# cc2651r3.net
KiCad netlist of a schematic drawn in EAGLE
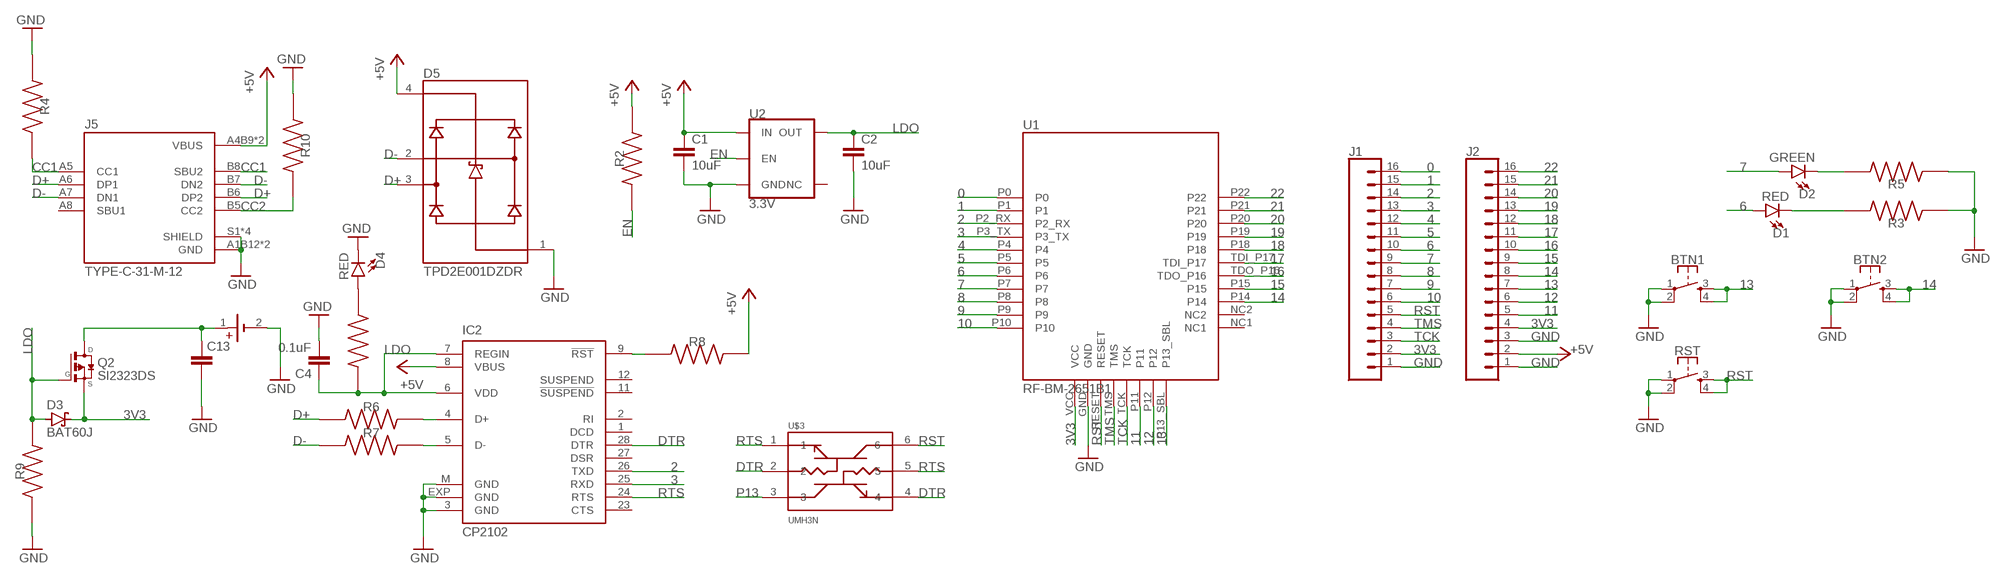
[diagram p0: schematic, sheet 1]

(export (version "E")
  (design (tool "Eeschema 10.0.6"))
  (components
    (comp (ref "BT2")
      (value "79527141")
      (footprint "eagle-import:79527141")
      (fields
        (field (name "DIGIKEY_PART_NO") "732-12325-2-ND")
        (field (name "MANUFACTURER") "Wurth Electronics Inc.")
        (field (name "CREATED_BY") "PCBLayout.com")
      )
      (libsource (lib "eagle-import") (part "79527141"))
    )
    (comp (ref "BTN1")
      (value "MOMENTARY-SWITCH-SPST-2-SMD-4.6X2.8MM")
      (footprint "eagle-import:TACTILE_SWITCH_SMD_4.6X2.8MM")
      (libsource (lib "eagle-import") (part "MOMENTARY-SWITCH-SPST-2-SMD-4.6X2.8MM"))
    )
    (comp (ref "BTN2")
      (value "MOMENTARY-SWITCH-SPST-2-SMD-4.6X2.8MM")
      (footprint "eagle-import:TACTILE_SWITCH_SMD_4.6X2.8MM")
      (libsource (lib "eagle-import") (part "MOMENTARY-SWITCH-SPST-2-SMD-4.6X2.8MM"))
    )
    (comp (ref "C1")
      (value "10uF")
      (footprint "eagle-import:0603")
      (libsource (lib "eagle-import") (part "10UF-0603-6.3V-20%"))
    )
    (comp (ref "C2")
      (value "10uF")
      (footprint "eagle-import:0603")
      (libsource (lib "eagle-import") (part "10UF-0603-6.3V-20%"))
    )
    (comp (ref "C4")
      (value "0.1uF")
      (footprint "eagle-import:0603")
      (libsource (lib "eagle-import") (part "0.1UF-0603-25V-(+80/-20%)"))
    )
    (comp (ref "C13")
      (value "C_TANTALUM-2917(7343-METRIC)")
      (footprint "eagle-import:CAPM7343X310")
      (libsource (lib "eagle-import") (part "CTANTALUM-2917(7343-METRIC)_"))
    )
    (comp (ref "D1")
      (value "RED")
      (footprint "eagle-import:LED-0603")
      (libsource (lib "eagle-import") (part "LED-RED0603"))
    )
    (comp (ref "D2")
      (value "GREEN")
      (footprint "eagle-import:LED-0603")
      (libsource (lib "eagle-import") (part "LED-GREEN0603"))
    )
    (comp (ref "D3")
      (value "BAT60J")
      (footprint "eagle-import:SOD323_ST")
      (libsource (lib "eagle-import") (part "BAT60J"))
    )
    (comp (ref "D4")
      (value "RED")
      (footprint "eagle-import:LED-0603")
      (libsource (lib "eagle-import") (part "LED-RED0603"))
    )
    (comp (ref "D5")
      (value "TPD2E001DZDR")
      (footprint "eagle-import:SOT192P237X122-4N")
      (fields (field (name "MF") "Texas Instruments"))
      (libsource (lib "eagle-import") (part "TPD2E001DZDR"))
    )
    (comp (ref "IC2")
      (value "CP2102")
      (footprint "eagle-import:MLP28")
      (fields (field (name "MF") "FARNELL") (field (name "MPN") "CP2102-GM"))
      (libsource (lib "eagle-import") (part "CP2102"))
    )
    (comp (ref "J1")
      (value "CONN_161X16_NO_SILK")
      (footprint "eagle-import:1X16_NO_SILK")
      (libsource (lib "eagle-import") (part "CONN_161X16_NO_SILK"))
    )
    (comp (ref "J2")
      (value "CONN_161X16_NO_SILK")
      (footprint "eagle-import:1X16_NO_SILK")
      (libsource (lib "eagle-import") (part "CONN_161X16_NO_SILK"))
    )
    (comp (ref "J5")
      (value "TYPE-C-31-M-12")
      (footprint "eagle-import:HRO_TYPE-C-31-M-12")
      (fields (field (name "MF") "HRO Electronics Co., Ltd."))
      (libsource (lib "eagle-import") (part "TYPE-C-31-M-12"))
    )
    (comp (ref "Q2")
      (value "SI2323DS")
      (footprint "eagle-import:SOT23")
      (fields (field (name "MF") "Vishay Siliconix"))
      (libsource (lib "eagle-import") (part "SI2323DS"))
    )
    (comp (ref "R2")
      (value "RC0402FR-073M6L")
      (footprint "eagle-import:RESC1005X40N")
      (fields (field (name "MF") "Yageo"))
      (libsource (lib "eagle-import") (part "RC0402FR-073M6L"))
    )
    (comp (ref "R3")
      (value "RC0402FR-073M6L")
      (footprint "eagle-import:RESC1005X40N")
      (fields (field (name "MF") "Yageo"))
      (libsource (lib "eagle-import") (part "RC0402FR-073M6L"))
    )
    (comp (ref "R4")
      (value "RC0402FR-073M6L")
      (footprint "eagle-import:RESC1005X40N")
      (fields (field (name "MF") "Yageo"))
      (libsource (lib "eagle-import") (part "RC0402FR-073M6L"))
    )
    (comp (ref "R5")
      (value "RC0402FR-073M6L")
      (footprint "eagle-import:RESC1005X40N")
      (fields (field (name "MF") "Yageo"))
      (libsource (lib "eagle-import") (part "RC0402FR-073M6L"))
    )
    (comp (ref "R6")
      (value "RC0402FR-073M6L")
      (footprint "eagle-import:RESC1005X40N")
      (fields (field (name "MF") "Yageo"))
      (libsource (lib "eagle-import") (part "RC0402FR-073M6L"))
    )
    (comp (ref "R7")
      (value "RC0402FR-073M6L")
      (footprint "eagle-import:RESC1005X40N")
      (fields (field (name "MF") "Yageo"))
      (libsource (lib "eagle-import") (part "RC0402FR-073M6L"))
    )
    (comp (ref "R8")
      (value "RC0402FR-073M6L")
      (footprint "eagle-import:RESC1005X40N")
      (fields (field (name "MF") "Yageo"))
      (libsource (lib "eagle-import") (part "RC0402FR-073M6L"))
    )
    (comp (ref "R9")
      (value "RC0402FR-073M6L")
      (footprint "eagle-import:RESC1005X40N")
      (fields (field (name "MF") "Yageo"))
      (libsource (lib "eagle-import") (part "RC0402FR-073M6L"))
    )
    (comp (ref "R10")
      (value "RC0402FR-073M6L")
      (footprint "eagle-import:RESC1005X40N")
      (fields (field (name "MF") "Yageo"))
      (libsource (lib "eagle-import") (part "RC0402FR-073M6L"))
    )
    (comp (ref "R11")
      (value "RC0402FR-073M6L")
      (footprint "eagle-import:RESC1005X40N")
      (fields (field (name "MF") "Yageo"))
      (libsource (lib "eagle-import") (part "RC0402FR-073M6L"))
    )
    (comp (ref "RST")
      (value "MOMENTARY-SWITCH-SPST-2-SMD-4.6X2.8MM")
      (footprint "eagle-import:TACTILE_SWITCH_SMD_4.6X2.8MM")
      (libsource (lib "eagle-import") (part "MOMENTARY-SWITCH-SPST-2-SMD-4.6X2.8MM"))
    )
    (comp (ref "U$3")
      (value "UMH3N")
      (footprint "eagle-import:SOP65P210X100-6N")
      (fields (field (name "MF") "Rohm"))
      (libsource (lib "eagle-import") (part "UMH3N"))
    )
    (comp (ref "U1")
      (value "RF-BM-2651B1")
      (footprint "eagle-import:RF-BM-2651B1")
      (libsource (lib "eagle-import") (part "RF-BM-2651B1"))
    )
    (comp (ref "U2")
      (value "3.3V")
      (footprint "eagle-import:SOT23-5")
      (libsource (lib "eagle-import") (part "V_REG_AP2112K-3.3V"))
    )
  )
  (nets
    (net (code "1") (name "+5V") (class "Default")
      (node (ref "C1") (pin "1") (pinfunction "1_1") (pintype "passive"))
      (node (ref "D5") (pin "4") (pinfunction "VCC_4") (pintype "power_in"))
      (node (ref "IC2") (pin "8") (pinfunction "VBUS_8") (pintype "input"))
      (node (ref "J2") (pin "2") (pinfunction "2_2") (pintype "passive"))
      (node (ref "J5") (pin "A4B9") (pinfunction "VBUS_A4B9") (pintype "power_in"))
      (node (ref "J5") (pin "B4A9") (pinfunction "VBUS_B4A9") (pintype "power_in"))
      (node (ref "R2") (pin "2") (pinfunction "2_2") (pintype "passive"))
      (node (ref "R8") (pin "2") (pinfunction "2_2") (pintype "passive"))
      (node (ref "U2") (pin "1") (pinfunction "IN_1") (pintype "input"))
    )
    (net (code "2") (name "/0") (class "Default")
      (node (ref "J1") (pin "16") (pinfunction "16_16") (pintype "passive"))
      (node (ref "U1") (pin "P0") (pinfunction "P0_P0") (pintype "bidirectional"))
    )
    (net (code "3") (name "/1") (class "Default")
      (node (ref "J1") (pin "15") (pinfunction "15_15") (pintype "passive"))
      (node (ref "U1") (pin "P1") (pinfunction "P1_P1") (pintype "bidirectional"))
    )
    (net (code "4") (name "/2") (class "Default")
      (node (ref "IC2") (pin "26") (pinfunction "TXD_26") (pintype "output"))
      (node (ref "J1") (pin "14") (pinfunction "14_14") (pintype "passive"))
      (node (ref "U1") (pin "P2_RX") (pinfunction "P2_RX_P2_RX") (pintype "bidirectional"))
    )
    (net (code "5") (name "/3") (class "Default")
      (node (ref "IC2") (pin "25") (pinfunction "RXD_25") (pintype "input"))
      (node (ref "J1") (pin "13") (pinfunction "13_13") (pintype "passive"))
      (node (ref "U1") (pin "P3_TX") (pinfunction "P3_TX_P3_TX") (pintype "bidirectional"))
    )
    (net (code "6") (name "/3V3") (class "Default")
      (node (ref "D3") (pin "C") (pinfunction "C_C") (pintype "passive"))
      (node (ref "J1") (pin "2") (pinfunction "2_2") (pintype "passive"))
      (node (ref "J2") (pin "4") (pinfunction "4_4") (pintype "passive"))
      (node (ref "Q2") (pin "2") (pinfunction "S_2") (pintype "passive"))
      (node (ref "U1") (pin "VCC") (pinfunction "VCC_VCC") (pintype "bidirectional"))
    )
    (net (code "7") (name "/4") (class "Default")
      (node (ref "J1") (pin "12") (pinfunction "12_12") (pintype "passive"))
      (node (ref "U1") (pin "P4") (pinfunction "P4_P4") (pintype "bidirectional"))
    )
    (net (code "8") (name "/5") (class "Default")
      (node (ref "J1") (pin "11") (pinfunction "11_11") (pintype "passive"))
      (node (ref "U1") (pin "P5") (pinfunction "P5_P5") (pintype "bidirectional"))
    )
    (net (code "9") (name "/6") (class "Default")
      (node (ref "D1") (pin "A") (pinfunction "A_A") (pintype "passive"))
      (node (ref "J1") (pin "10") (pinfunction "10_10") (pintype "passive"))
      (node (ref "U1") (pin "P6") (pinfunction "P6_P6") (pintype "bidirectional"))
    )
    (net (code "10") (name "/7") (class "Default")
      (node (ref "D2") (pin "A") (pinfunction "A_A") (pintype "passive"))
      (node (ref "J1") (pin "9") (pinfunction "9_9") (pintype "passive"))
      (node (ref "U1") (pin "P7") (pinfunction "P7_P7") (pintype "bidirectional"))
    )
    (net (code "11") (name "/8") (class "Default")
      (node (ref "J1") (pin "8") (pinfunction "8_8") (pintype "passive"))
      (node (ref "U1") (pin "P8") (pinfunction "P8_P8") (pintype "bidirectional"))
    )
    (net (code "12") (name "/9") (class "Default")
      (node (ref "J1") (pin "7") (pinfunction "7_7") (pintype "passive"))
      (node (ref "U1") (pin "P9") (pinfunction "P9_P9") (pintype "bidirectional"))
    )
    (net (code "13") (name "/10") (class "Default")
      (node (ref "J1") (pin "6") (pinfunction "6_6") (pintype "passive"))
      (node (ref "U1") (pin "P10") (pinfunction "P10_P10") (pintype "bidirectional"))
    )
    (net (code "14") (name "/11") (class "Default")
      (node (ref "J2") (pin "5") (pinfunction "5_5") (pintype "passive"))
      (node (ref "U1") (pin "P11") (pinfunction "P11_P11") (pintype "bidirectional"))
    )
    (net (code "15") (name "/12") (class "Default")
      (node (ref "J2") (pin "6") (pinfunction "6_6") (pintype "passive"))
      (node (ref "U1") (pin "P12") (pinfunction "P12_P12") (pintype "bidirectional"))
    )
    (net (code "16") (name "/13") (class "Default")
      (node (ref "BTN1") (pin "3") (pinfunction "3_3") (pintype "passive"))
      (node (ref "BTN1") (pin "4") (pinfunction "4_4") (pintype "passive"))
      (node (ref "J2") (pin "7") (pinfunction "7_7") (pintype "passive"))
      (node (ref "U1") (pin "P13_SBL") (pinfunction "P13_SBL_P13_SBL") (pintype "bidirectional"))
    )
    (net (code "17") (name "/14") (class "Default")
      (node (ref "BTN2") (pin "3") (pinfunction "3_3") (pintype "passive"))
      (node (ref "BTN2") (pin "4") (pinfunction "4_4") (pintype "passive"))
      (node (ref "J2") (pin "8") (pinfunction "8_8") (pintype "passive"))
      (node (ref "U1") (pin "P14") (pinfunction "P14_P14") (pintype "bidirectional"))
    )
    (net (code "18") (name "/15") (class "Default")
      (node (ref "J2") (pin "9") (pinfunction "9_9") (pintype "passive"))
      (node (ref "U1") (pin "P15") (pinfunction "P15_P15") (pintype "bidirectional"))
    )
    (net (code "19") (name "/16") (class "Default")
      (node (ref "J2") (pin "10") (pinfunction "10_10") (pintype "passive"))
      (node (ref "U1") (pin "TDO_P16") (pinfunction "TDO_P16_TDO_P16") (pintype "bidirectional"))
    )
    (net (code "20") (name "/17") (class "Default")
      (node (ref "J2") (pin "11") (pinfunction "11_11") (pintype "passive"))
      (node (ref "U1") (pin "TDI_P17") (pinfunction "TDI_P17_TDI_P17") (pintype "bidirectional"))
    )
    (net (code "21") (name "/18") (class "Default")
      (node (ref "J2") (pin "12") (pinfunction "12_12") (pintype "passive"))
      (node (ref "U1") (pin "P18") (pinfunction "P18_P18") (pintype "bidirectional"))
    )
    (net (code "22") (name "/19") (class "Default")
      (node (ref "J2") (pin "13") (pinfunction "13_13") (pintype "passive"))
      (node (ref "U1") (pin "P19") (pinfunction "P19_P19") (pintype "bidirectional"))
    )
    (net (code "23") (name "/20") (class "Default")
      (node (ref "J2") (pin "14") (pinfunction "14_14") (pintype "passive"))
      (node (ref "U1") (pin "P20") (pinfunction "P20_P20") (pintype "bidirectional"))
    )
    (net (code "24") (name "/21") (class "Default")
      (node (ref "J2") (pin "15") (pinfunction "15_15") (pintype "passive"))
      (node (ref "U1") (pin "P21") (pinfunction "P21_P21") (pintype "bidirectional"))
    )
    (net (code "25") (name "/22") (class "Default")
      (node (ref "J2") (pin "16") (pinfunction "16_16") (pintype "passive"))
      (node (ref "U1") (pin "P22") (pinfunction "P22_P22") (pintype "bidirectional"))
    )
    (net (code "26") (name "/CC1") (class "Default")
      (node (ref "J5") (pin "A5") (pinfunction "CC1_A5") (pintype "bidirectional"))
      (node (ref "J5") (pin "B8") (pinfunction "SBU2_B8") (pintype "bidirectional"))
      (node (ref "R4") (pin "2") (pinfunction "2_2") (pintype "passive"))
    )
    (net (code "27") (name "/CC2") (class "Default")
      (node (ref "J5") (pin "B5") (pinfunction "CC2_B5") (pintype "bidirectional"))
      (node (ref "R10") (pin "2") (pinfunction "2_2") (pintype "passive"))
    )
    (net (code "28") (name "/D+") (class "Default")
      (node (ref "D5") (pin "3") (pinfunction "IO2_3") (pintype "bidirectional"))
      (node (ref "J5") (pin "A6") (pinfunction "DP1_A6") (pintype "bidirectional"))
      (node (ref "J5") (pin "B6") (pinfunction "DP2_B6") (pintype "bidirectional"))
      (node (ref "R6") (pin "1") (pinfunction "1_1") (pintype "passive"))
    )
    (net (code "29") (name "/D-") (class "Default")
      (node (ref "D5") (pin "2") (pinfunction "IO1_2") (pintype "bidirectional"))
      (node (ref "J5") (pin "A7") (pinfunction "DN1_A7") (pintype "bidirectional"))
      (node (ref "J5") (pin "B7") (pinfunction "DN2_B7") (pintype "bidirectional"))
      (node (ref "R7") (pin "1") (pinfunction "1_1") (pintype "passive"))
    )
    (net (code "30") (name "/DTR") (class "Default")
      (node (ref "IC2") (pin "28") (pinfunction "DTR_28") (pintype "output"))
      (node (ref "U$3") (pin "2") (pinfunction "2_2") (pintype "bidirectional"))
      (node (ref "U$3") (pin "4") (pinfunction "4_4") (pintype "bidirectional"))
    )
    (net (code "31") (name "/EN") (class "Default")
      (node (ref "R2") (pin "1") (pinfunction "1_1") (pintype "passive"))
      (node (ref "U2") (pin "3") (pinfunction "EN_3") (pintype "input"))
    )
    (net (code "32") (name "/LDO") (class "Default")
      (node (ref "C2") (pin "1") (pinfunction "1_1") (pintype "passive"))
      (node (ref "C4") (pin "1") (pinfunction "1_1") (pintype "passive"))
      (node (ref "D3") (pin "A") (pinfunction "A_A") (pintype "passive"))
      (node (ref "IC2") (pin "6") (pinfunction "VDD_6") (pintype "power_in"))
      (node (ref "IC2") (pin "7") (pinfunction "REGIN_7") (pintype "passive"))
      (node (ref "Q2") (pin "1") (pinfunction "G_1") (pintype "passive"))
      (node (ref "R11") (pin "2") (pinfunction "2_2") (pintype "passive"))
      (node (ref "R9") (pin "2") (pinfunction "2_2") (pintype "passive"))
      (node (ref "U2") (pin "5") (pinfunction "OUT_5") (pintype "passive"))
    )
    (net (code "33") (name "/P13") (class "Default")
      (node (ref "U$3") (pin "3") (pinfunction "3_3") (pintype "bidirectional"))
    )
    (net (code "34") (name "/RST") (class "Default")
      (node (ref "J1") (pin "5") (pinfunction "5_5") (pintype "passive"))
      (node (ref "RST") (pin "3") (pinfunction "3_3") (pintype "passive"))
      (node (ref "RST") (pin "4") (pinfunction "4_4") (pintype "passive"))
      (node (ref "U$3") (pin "6") (pinfunction "6_6") (pintype "bidirectional"))
      (node (ref "U1") (pin "RESET") (pinfunction "RESET_RESET") (pintype "bidirectional"))
    )
    (net (code "35") (name "/RTS") (class "Default")
      (node (ref "IC2") (pin "24") (pinfunction "RTS_24") (pintype "output"))
      (node (ref "U$3") (pin "1") (pinfunction "1_1") (pintype "bidirectional"))
      (node (ref "U$3") (pin "5") (pinfunction "5_5") (pintype "bidirectional"))
    )
    (net (code "36") (name "/TCK") (class "Default")
      (node (ref "J1") (pin "3") (pinfunction "3_3") (pintype "passive"))
      (node (ref "U1") (pin "TCK") (pinfunction "TCK_TCK") (pintype "bidirectional"))
    )
    (net (code "37") (name "/TMS") (class "Default")
      (node (ref "J1") (pin "4") (pinfunction "4_4") (pintype "passive"))
      (node (ref "U1") (pin "TMS") (pinfunction "TMS_TMS") (pintype "bidirectional"))
    )
    (net (code "38") (name "GND") (class "Default")
      (node (ref "BT2") (pin "2") (pinfunction "-_2") (pintype "passive"))
      (node (ref "BTN1") (pin "1") (pinfunction "1_1") (pintype "passive"))
      (node (ref "BTN1") (pin "2") (pinfunction "2_2") (pintype "passive"))
      (node (ref "BTN2") (pin "1") (pinfunction "1_1") (pintype "passive"))
      (node (ref "BTN2") (pin "2") (pinfunction "2_2") (pintype "passive"))
      (node (ref "C1") (pin "2") (pinfunction "2_2") (pintype "passive"))
      (node (ref "C13") (pin "2") (pinfunction "2_2") (pintype "passive"))
      (node (ref "C2") (pin "2") (pinfunction "2_2") (pintype "passive"))
      (node (ref "C4") (pin "2") (pinfunction "2_2") (pintype "passive"))
      (node (ref "D4") (pin "C") (pinfunction "C_C") (pintype "passive"))
      (node (ref "D5") (pin "1") (pinfunction "GND_1") (pintype "power_in"))
      (node (ref "IC2") (pin "3") (pinfunction "GND_3") (pintype "power_in"))
      (node (ref "IC2") (pin "EXP") (pinfunction "GND_EXP") (pintype "power_in"))
      (node (ref "IC2") (pin "M") (pinfunction "GND_M") (pintype "power_in"))
      (node (ref "J1") (pin "1") (pinfunction "1_1") (pintype "passive"))
      (node (ref "J2") (pin "1") (pinfunction "1_1") (pintype "passive"))
      (node (ref "J2") (pin "3") (pinfunction "3_3") (pintype "passive"))
      (node (ref "J5") (pin "A1B12") (pinfunction "GND_A1B12") (pintype "power_in"))
      (node (ref "J5") (pin "B1A12") (pinfunction "GND_B1A12") (pintype "power_in"))
      (node (ref "J5") (pin "S1") (pinfunction "SHIELD_S1") (pintype "passive"))
      (node (ref "J5") (pin "S2") (pinfunction "SHIELD_S2") (pintype "passive"))
      (node (ref "J5") (pin "S3") (pinfunction "SHIELD_S3") (pintype "passive"))
      (node (ref "J5") (pin "S4") (pinfunction "SHIELD_S4") (pintype "passive"))
      (node (ref "R10") (pin "1") (pinfunction "1_1") (pintype "passive"))
      (node (ref "R3") (pin "1") (pinfunction "1_1") (pintype "passive"))
      (node (ref "R4") (pin "1") (pinfunction "1_1") (pintype "passive"))
      (node (ref "R5") (pin "1") (pinfunction "1_1") (pintype "passive"))
      (node (ref "R9") (pin "1") (pinfunction "1_1") (pintype "passive"))
      (node (ref "RST") (pin "1") (pinfunction "1_1") (pintype "passive"))
      (node (ref "RST") (pin "2") (pinfunction "2_2") (pintype "passive"))
      (node (ref "U1") (pin "GND") (pinfunction "GND_GND") (pintype "bidirectional"))
      (node (ref "U2") (pin "2") (pinfunction "GND_2") (pintype "input"))
    )
    (net (code "39") (name "Net-(BT2-+)") (class "Default")
      (node (ref "BT2") (pin "1") (pinfunction "+_1") (pintype "passive"))
      (node (ref "C13") (pin "1") (pinfunction "1_1") (pintype "passive"))
      (node (ref "Q2") (pin "3") (pinfunction "D_3") (pintype "passive"))
    )
    (net (code "40") (name "Net-(D1-PadC)") (class "Default")
      (node (ref "D1") (pin "C") (pinfunction "C_C") (pintype "passive"))
      (node (ref "R3") (pin "2") (pinfunction "2_2") (pintype "passive"))
    )
    (net (code "41") (name "Net-(D2-PadC)") (class "Default")
      (node (ref "D2") (pin "C") (pinfunction "C_C") (pintype "passive"))
      (node (ref "R5") (pin "2") (pinfunction "2_2") (pintype "passive"))
    )
    (net (code "42") (name "Net-(D4-PadA)") (class "Default")
      (node (ref "D4") (pin "A") (pinfunction "A_A") (pintype "passive"))
      (node (ref "R11") (pin "1") (pinfunction "1_1") (pintype "passive"))
    )
    (net (code "43") (name "Net-(IC2-D+)") (class "Default")
      (node (ref "IC2") (pin "4") (pinfunction "D+_4") (pintype "bidirectional"))
      (node (ref "R6") (pin "2") (pinfunction "2_2") (pintype "passive"))
    )
    (net (code "44") (name "Net-(IC2-D-)") (class "Default")
      (node (ref "IC2") (pin "5") (pinfunction "D-_5") (pintype "bidirectional"))
      (node (ref "R7") (pin "2") (pinfunction "2_2") (pintype "passive"))
    )
    (net (code "45") (name "Net-(IC2-~{RST})") (class "Default")
      (node (ref "IC2") (pin "9") (pinfunction "~{RST}_9") (pintype "bidirectional"))
      (node (ref "R8") (pin "1") (pinfunction "1_1") (pintype "passive"))
    )
    (net (code "46") (name "unconnected-(IC2-CTS-Pad23)") (class "Default")
      (node (ref "IC2") (pin "23") (pinfunction "CTS_23") (pintype "input"))
    )
    (net (code "47") (name "unconnected-(IC2-DCD-Pad1)") (class "Default")
      (node (ref "IC2") (pin "1") (pinfunction "DCD_1") (pintype "input"))
    )
    (net (code "48") (name "unconnected-(IC2-DSR-Pad27)") (class "Default")
      (node (ref "IC2") (pin "27") (pinfunction "DSR_27") (pintype "input"))
    )
    (net (code "49") (name "unconnected-(IC2-RI-Pad2)") (class "Default")
      (node (ref "IC2") (pin "2") (pinfunction "RI_2") (pintype "input"))
    )
    (net (code "50") (name "unconnected-(IC2-SUSPEND-Pad12)") (class "Default")
      (node (ref "IC2") (pin "12") (pinfunction "SUSPEND_12") (pintype "output"))
    )
    (net (code "51") (name "unconnected-(IC2-~{SUSPEND}-Pad11)") (class "Default")
      (node (ref "IC2") (pin "11") (pinfunction "~{SUSPEND}_11") (pintype "output"))
    )
    (net (code "52") (name "unconnected-(J5-SBU1-PadA8)") (class "Default")
      (node (ref "J5") (pin "A8") (pinfunction "SBU1_A8") (pintype "bidirectional"))
    )
    (net (code "53") (name "unconnected-(U1-PadNC1)") (class "Default")
      (node (ref "U1") (pin "NC1") (pinfunction "NC1_NC1") (pintype "bidirectional"))
    )
    (net (code "54") (name "unconnected-(U1-PadNC2)") (class "Default")
      (node (ref "U1") (pin "NC2") (pinfunction "NC2_NC2") (pintype "bidirectional"))
    )
    (net (code "55") (name "unconnected-(U2-NC-Pad4)") (class "Default")
      (node (ref "U2") (pin "4") (pinfunction "NC_4") (pintype "no_connect"))
    )
  )
)
